# Controller_final.net
KiCad netlist of a schematic drawn in Altium Designer
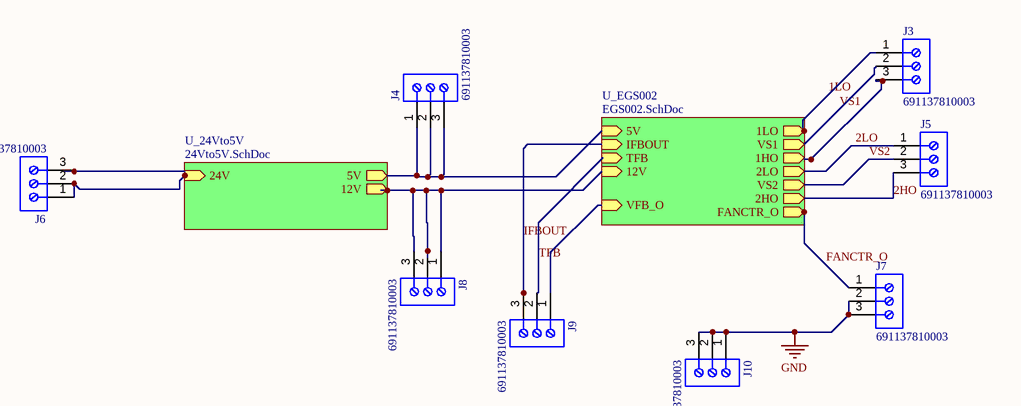
[diagram p0: Controller_final.SchDoc]

(export (version "E")
  (design (tool "Eeschema 10.0.6"))
  (components
    (comp (ref "J3")
      (value "691137810003")
      (footprint "691137810003")
      (description "10.00 mm Terminal Block, Horizontal Entr")
      (libsource (lib "Altium Content Vault") (part "TBL - 1R - 03P - Screw"))
    )
    (comp (ref "J4")
      (value "691137810003")
      (footprint "691137810003")
      (description "10.00 mm Terminal Block, Horizontal Entr")
      (libsource (lib "Altium Content Vault") (part "TBL - 1R - 03P - Screw"))
    )
    (comp (ref "J5")
      (value "691137810003")
      (footprint "691137810003")
      (description "10.00 mm Terminal Block, Horizontal Entr")
      (libsource (lib "Altium Content Vault") (part "TBL - 1R - 03P - Screw"))
    )
    (comp (ref "J6")
      (value "691137810003")
      (footprint "691137810003")
      (description "10.00 mm Terminal Block, Horizontal Entr")
      (libsource (lib "Altium Content Vault") (part "TBL - 1R - 03P - Screw"))
    )
    (comp (ref "J7")
      (value "691137810003")
      (footprint "691137810003")
      (description "10.00 mm Terminal Block, Horizontal Entr")
      (libsource (lib "Altium Content Vault") (part "TBL - 1R - 03P - Screw"))
    )
    (comp (ref "J8")
      (value "691137810003")
      (footprint "691137810003")
      (description "10.00 mm Terminal Block, Horizontal Entr")
      (libsource (lib "Altium Content Vault") (part "TBL - 1R - 03P - Screw"))
    )
    (comp (ref "J9")
      (value "691137810003")
      (footprint "691137810003")
      (description "10.00 mm Terminal Block, Horizontal Entr")
      (libsource (lib "Altium Content Vault") (part "TBL - 1R - 03P - Screw"))
    )
    (comp (ref "J10")
      (value "691137810003")
      (footprint "691137810003")
      (description "10.00 mm Terminal Block, Horizontal Entr")
      (libsource (lib "Altium Content Vault") (part "TBL - 1R - 03P - Screw"))
    )
  )
  (nets
    (net (code "1") (name "/1HO") (class "Default")
      (node (ref "J3") (pin "3") (pinfunction "3_3") (pintype "passive"))
    )
    (net (code "2") (name "/1LO") (class "Default")
      (node (ref "J3") (pin "1") (pinfunction "1_1") (pintype "passive"))
    )
    (net (code "3") (name "/2HO") (class "Default")
      (node (ref "J5") (pin "3") (pinfunction "3_3") (pintype "passive"))
    )
    (net (code "4") (name "/2LO") (class "Default")
      (node (ref "J5") (pin "1") (pinfunction "1_1") (pintype "passive"))
    )
    (net (code "5") (name "/5V") (class "Default")
      (node (ref "J4") (pin "1") (pinfunction "1_1") (pintype "passive"))
      (node (ref "J4") (pin "2") (pinfunction "2_2") (pintype "passive"))
      (node (ref "J4") (pin "3") (pinfunction "3_3") (pintype "passive"))
    )
    (net (code "6") (name "/12V") (class "Default")
      (node (ref "J8") (pin "1") (pinfunction "1_1") (pintype "passive"))
      (node (ref "J8") (pin "2") (pinfunction "2_2") (pintype "passive"))
      (node (ref "J8") (pin "3") (pinfunction "3_3") (pintype "passive"))
    )
    (net (code "7") (name "/24V") (class "Default")
      (node (ref "J6") (pin "1") (pinfunction "1_1") (pintype "passive"))
      (node (ref "J6") (pin "2") (pinfunction "2_2") (pintype "passive"))
      (node (ref "J6") (pin "3") (pinfunction "3_3") (pintype "passive"))
    )
    (net (code "8") (name "/FANCTR_O") (class "Default")
      (node (ref "J7") (pin "1") (pinfunction "1_1") (pintype "passive"))
    )
    (net (code "9") (name "/IFBOUT") (class "Default")
      (node (ref "J9") (pin "3") (pinfunction "3_3") (pintype "passive"))
    )
    (net (code "10") (name "/TFB") (class "Default")
      (node (ref "J9") (pin "2") (pinfunction "2_2") (pintype "passive"))
    )
    (net (code "11") (name "/VFB_O") (class "Default")
      (node (ref "J9") (pin "1") (pinfunction "1_1") (pintype "passive"))
    )
    (net (code "12") (name "/VS1") (class "Default")
      (node (ref "J3") (pin "2") (pinfunction "2_2") (pintype "passive"))
    )
    (net (code "13") (name "/VS2") (class "Default")
      (node (ref "J5") (pin "2") (pinfunction "2_2") (pintype "passive"))
    )
    (net (code "14") (name "GND") (class "Default")
      (node (ref "J10") (pin "1") (pinfunction "1_1") (pintype "passive"))
      (node (ref "J10") (pin "2") (pinfunction "2_2") (pintype "passive"))
      (node (ref "J10") (pin "3") (pinfunction "3_3") (pintype "passive"))
      (node (ref "J7") (pin "2") (pinfunction "2_2") (pintype "passive"))
      (node (ref "J7") (pin "3") (pinfunction "3_3") (pintype "passive"))
    )
  )
)
